# Ethernet.net
KiCad netlist of a schematic drawn in Altium Designer
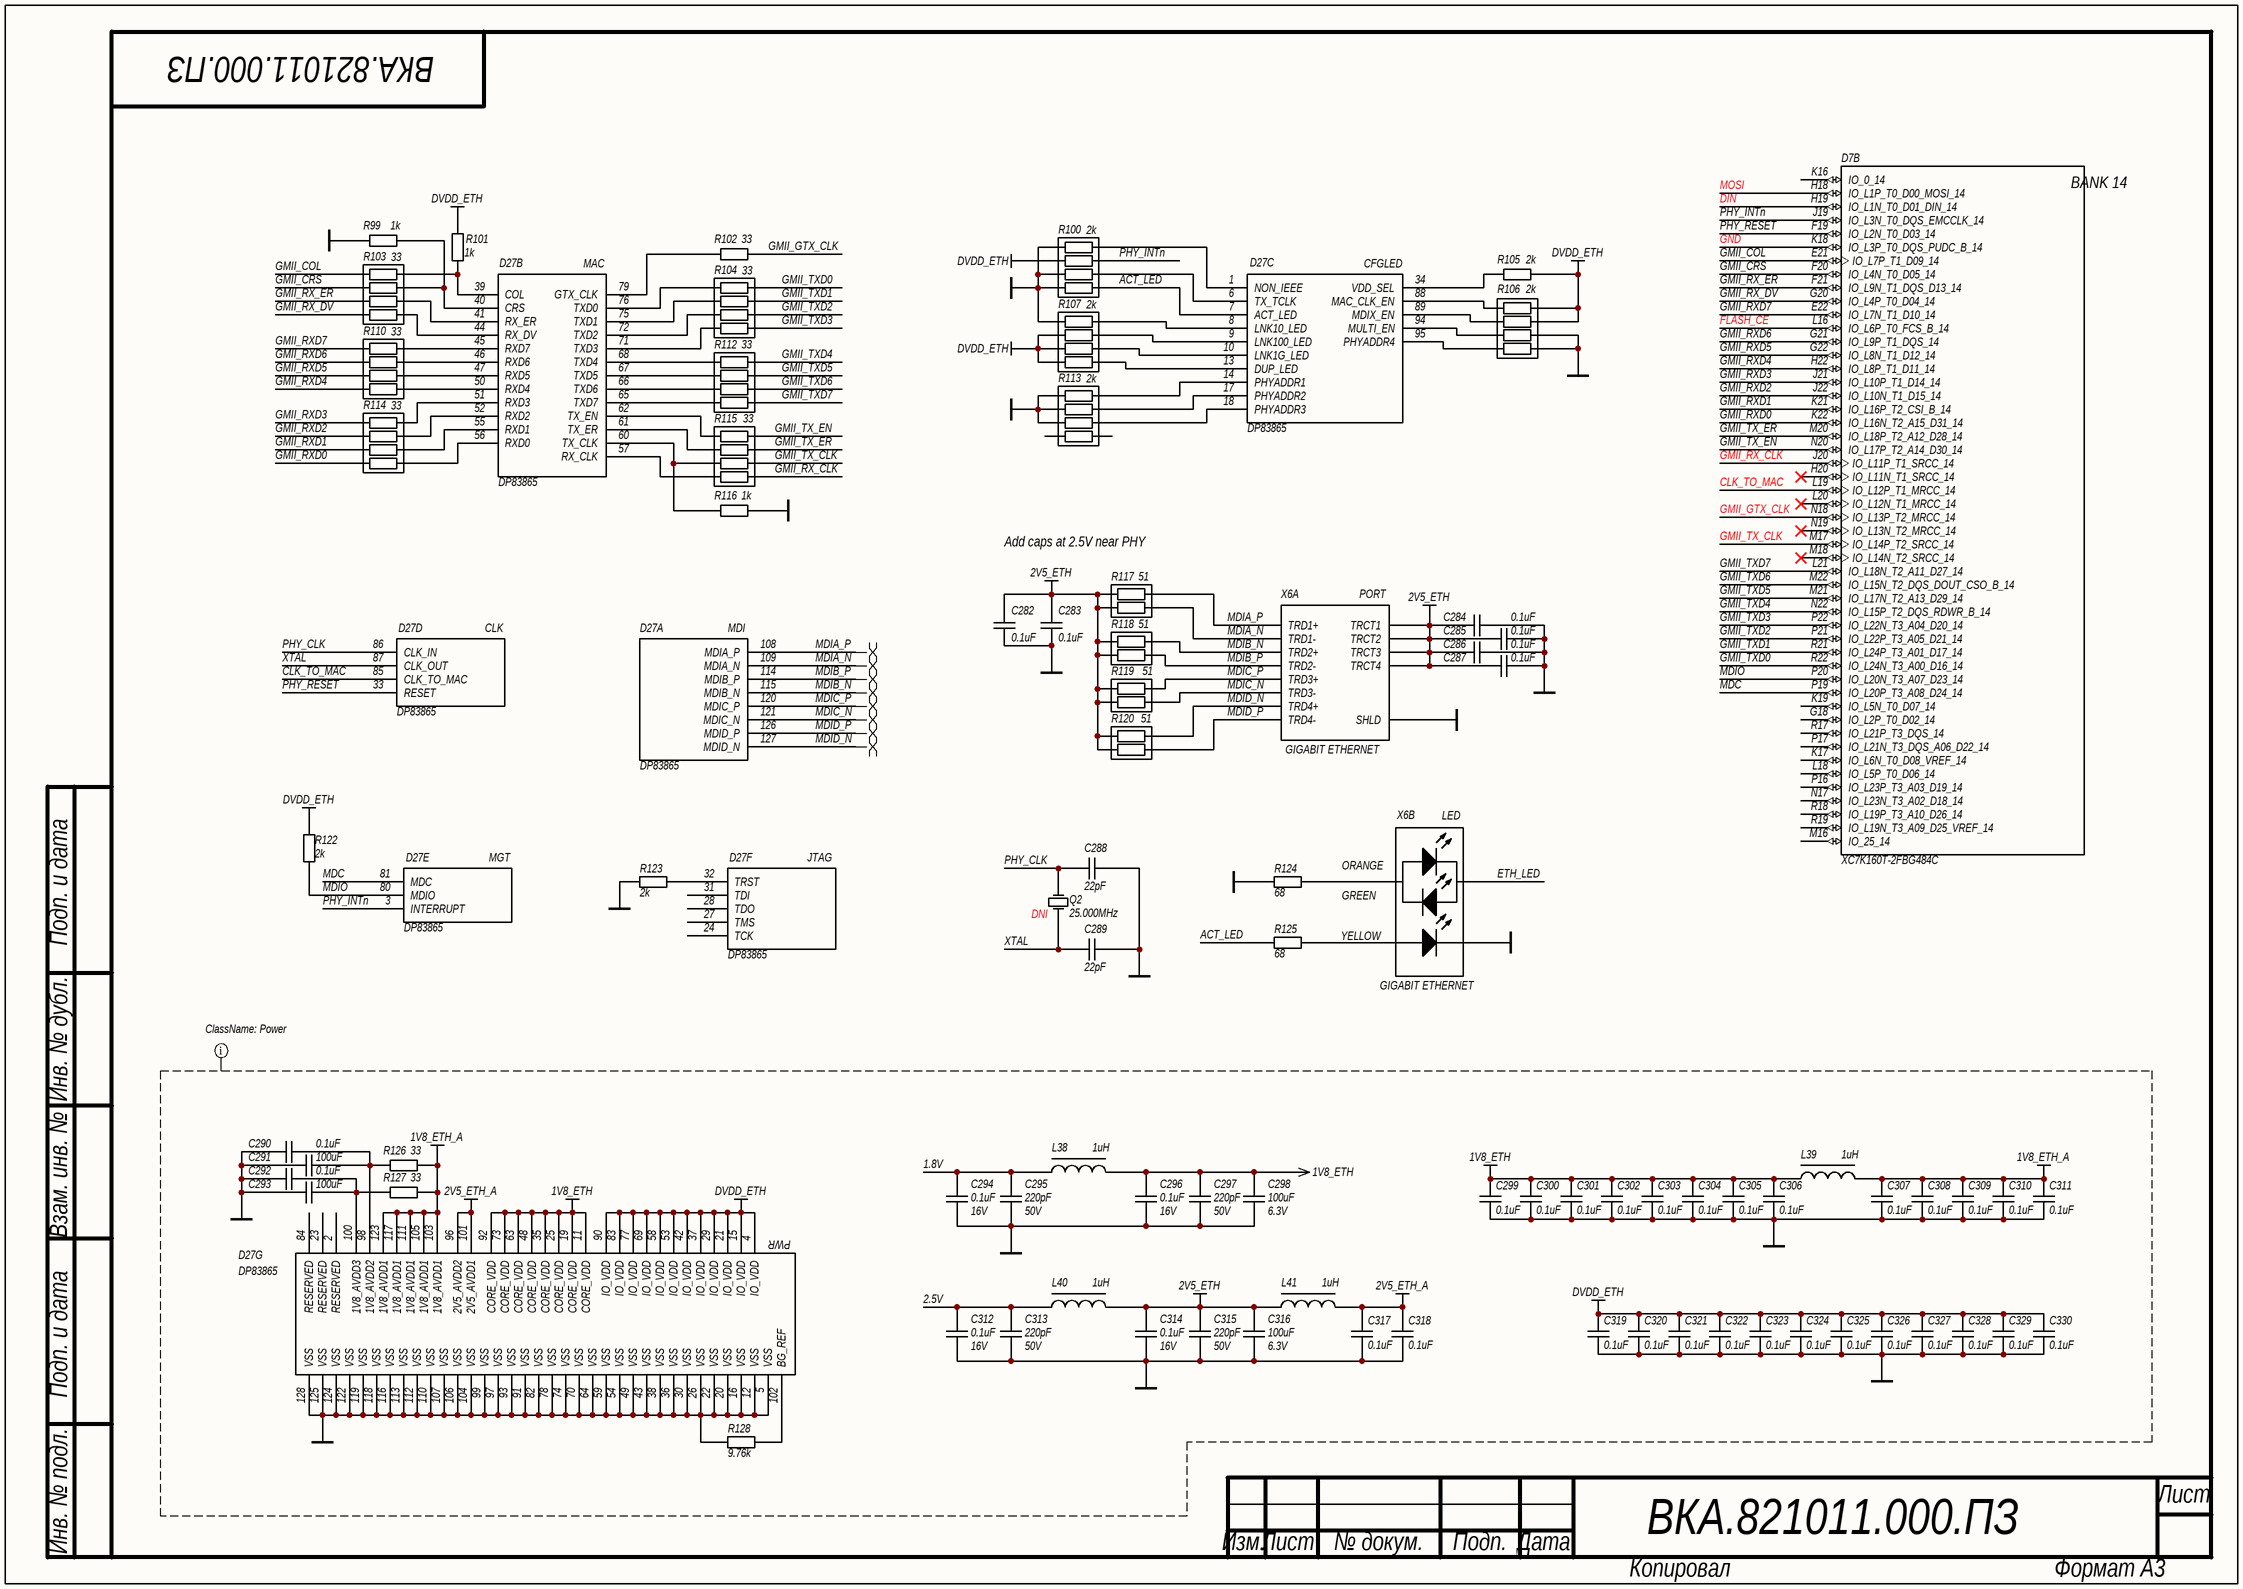
[diagram p0: Ethernet.SchDoc]

(export (version "E")
  (design (tool "Eeschema 10.0.6"))
  (components
    (comp (ref "C282")
      (value "0.1uF")
      (footprint "C0402")
      (description "SMD Capacitor")
      (fields (field (name "MANUFACTURER") "Murata") (field (name "TOLERANCE") "10%"))
      (libsource (lib "Kintex_SDR") (part "CAP"))
    )
    (comp (ref "C283")
      (value "0.1uF")
      (footprint "C0402")
      (description "SMD Capacitor")
      (fields (field (name "MANUFACTURER") "Murata") (field (name "TOLERANCE") "10%"))
      (libsource (lib "Kintex_SDR") (part "CAP"))
    )
    (comp (ref "C284")
      (value "0.1uF")
      (footprint "C0402")
      (description "SMD Capacitor")
      (fields (field (name "MANUFACTURER") "Murata") (field (name "TOLERANCE") "10%"))
      (libsource (lib "Kintex_SDR") (part "CAP"))
    )
    (comp (ref "C285")
      (value "0.1uF")
      (footprint "C0402")
      (description "SMD Capacitor")
      (fields (field (name "MANUFACTURER") "Murata") (field (name "TOLERANCE") "10%"))
      (libsource (lib "Kintex_SDR") (part "CAP"))
    )
    (comp (ref "C286")
      (value "0.1uF")
      (footprint "C0402")
      (description "SMD Capacitor")
      (fields (field (name "MANUFACTURER") "Murata") (field (name "TOLERANCE") "10%"))
      (libsource (lib "Kintex_SDR") (part "CAP"))
    )
    (comp (ref "C287")
      (value "0.1uF")
      (footprint "C0402")
      (description "SMD Capacitor")
      (fields (field (name "MANUFACTURER") "Murata") (field (name "TOLERANCE") "10%"))
      (libsource (lib "Kintex_SDR") (part "CAP"))
    )
    (comp (ref "C288")
      (value "22pF")
      (footprint "C0402")
      (description "SMD Capacitor")
      (fields (field (name "MANUFACTURER") "Murata") (field (name "TOLERANCE") "1%"))
      (libsource (lib "Kintex_SDR") (part "CAP"))
    )
    (comp (ref "C289")
      (value "22pF")
      (footprint "C0402")
      (description "SMD Capacitor")
      (fields (field (name "MANUFACTURER") "Murata") (field (name "TOLERANCE") "1%"))
      (libsource (lib "Kintex_SDR") (part "CAP"))
    )
    (comp (ref "C290")
      (value "0.1uF")
      (footprint "C0402")
      (description "SMD Capacitor")
      (fields (field (name "MANUFACTURER") "Murata") (field (name "TOLERANCE") "10%"))
      (libsource (lib "Kintex_SDR") (part "CAP"))
    )
    (comp (ref "C291")
      (value "100uF")
      (footprint "C1210")
      (description "SMD Capacitor")
      (fields (field (name "MANUFACTURER") "Murata") (field (name "TOLERANCE") "20%"))
      (libsource (lib "Kintex_SDR") (part "CAP uF"))
    )
    (comp (ref "C292")
      (value "0.1uF")
      (footprint "C0402")
      (description "SMD Capacitor")
      (fields (field (name "MANUFACTURER") "Murata") (field (name "TOLERANCE") "10%"))
      (libsource (lib "Kintex_SDR") (part "CAP"))
    )
    (comp (ref "C293")
      (value "100uF")
      (footprint "C1210")
      (description "SMD Capacitor")
      (fields (field (name "MANUFACTURER") "Murata") (field (name "TOLERANCE") "20%"))
      (libsource (lib "Kintex_SDR") (part "CAP uF"))
    )
    (comp (ref "C294")
      (value "0.1uF")
      (footprint "C0603")
      (description "SMD Capacitor")
      (fields
        (field (name "MANUFACTURER") "Murata")
        (field (name "TOLERANCE") "10%")
        (field (name "VOLTAGE") "16V")
      )
      (libsource (lib "Kintex_SDR") (part "CAP"))
    )
    (comp (ref "C295")
      (value "220pF")
      (footprint "C0603")
      (description "SMD Capacitor")
      (fields
        (field (name "MANUFACTURER") "Murata")
        (field (name "TOLERANCE") "10%")
        (field (name "VOLTAGE") "50V")
      )
      (libsource (lib "Kintex_SDR") (part "CAP"))
    )
    (comp (ref "C296")
      (value "0.1uF")
      (footprint "C0603")
      (description "SMD Capacitor")
      (fields
        (field (name "MANUFACTURER") "Murata")
        (field (name "TOLERANCE") "10%")
        (field (name "VOLTAGE") "16V")
      )
      (libsource (lib "Kintex_SDR") (part "CAP"))
    )
    (comp (ref "C297")
      (value "220pF")
      (footprint "C0603")
      (description "SMD Capacitor")
      (fields
        (field (name "MANUFACTURER") "Murata")
        (field (name "TOLERANCE") "10%")
        (field (name "VOLTAGE") "50V")
      )
      (libsource (lib "Kintex_SDR") (part "CAP"))
    )
    (comp (ref "C298")
      (value "100uF")
      (footprint "C1210")
      (description "SMD Capacitor")
      (fields
        (field (name "MANUFACTURER") "Murata")
        (field (name "TOLERANCE") "20%")
        (field (name "VOLTAGE") "6.3V")
      )
      (libsource (lib "Kintex_SDR") (part "CAP uF"))
    )
    (comp (ref "C299")
      (value "0.1uF")
      (footprint "C0402")
      (description "SMD Capacitor")
      (fields (field (name "MANUFACTURER") "Murata") (field (name "TOLERANCE") "10%"))
      (libsource (lib "Kintex_SDR") (part "CAP"))
    )
    (comp (ref "C300")
      (value "0.1uF")
      (footprint "C0402")
      (description "SMD Capacitor")
      (fields (field (name "MANUFACTURER") "Murata") (field (name "TOLERANCE") "10%"))
      (libsource (lib "Kintex_SDR") (part "CAP"))
    )
    (comp (ref "C301")
      (value "0.1uF")
      (footprint "C0402")
      (description "SMD Capacitor")
      (fields (field (name "MANUFACTURER") "Murata") (field (name "TOLERANCE") "10%"))
      (libsource (lib "Kintex_SDR") (part "CAP"))
    )
    (comp (ref "C302")
      (value "0.1uF")
      (footprint "C0402")
      (description "SMD Capacitor")
      (fields (field (name "MANUFACTURER") "Murata") (field (name "TOLERANCE") "10%"))
      (libsource (lib "Kintex_SDR") (part "CAP"))
    )
    (comp (ref "C303")
      (value "0.1uF")
      (footprint "C0402")
      (description "SMD Capacitor")
      (fields (field (name "MANUFACTURER") "Murata") (field (name "TOLERANCE") "10%"))
      (libsource (lib "Kintex_SDR") (part "CAP"))
    )
    (comp (ref "C304")
      (value "0.1uF")
      (footprint "C0402")
      (description "SMD Capacitor")
      (fields (field (name "MANUFACTURER") "Murata") (field (name "TOLERANCE") "10%"))
      (libsource (lib "Kintex_SDR") (part "CAP"))
    )
    (comp (ref "C305")
      (value "0.1uF")
      (footprint "C0402")
      (description "SMD Capacitor")
      (fields (field (name "MANUFACTURER") "Murata") (field (name "TOLERANCE") "10%"))
      (libsource (lib "Kintex_SDR") (part "CAP"))
    )
    (comp (ref "C306")
      (value "0.1uF")
      (footprint "C0402")
      (description "SMD Capacitor")
      (fields (field (name "MANUFACTURER") "Murata") (field (name "TOLERANCE") "10%"))
      (libsource (lib "Kintex_SDR") (part "CAP"))
    )
    (comp (ref "C307")
      (value "0.1uF")
      (footprint "C0402")
      (description "SMD Capacitor")
      (fields (field (name "MANUFACTURER") "Murata") (field (name "TOLERANCE") "10%"))
      (libsource (lib "Kintex_SDR") (part "CAP"))
    )
    (comp (ref "C308")
      (value "0.1uF")
      (footprint "C0402")
      (description "SMD Capacitor")
      (fields (field (name "MANUFACTURER") "Murata") (field (name "TOLERANCE") "10%"))
      (libsource (lib "Kintex_SDR") (part "CAP"))
    )
    (comp (ref "C309")
      (value "0.1uF")
      (footprint "C0402")
      (description "SMD Capacitor")
      (fields (field (name "MANUFACTURER") "Murata") (field (name "TOLERANCE") "10%"))
      (libsource (lib "Kintex_SDR") (part "CAP"))
    )
    (comp (ref "C310")
      (value "0.1uF")
      (footprint "C0402")
      (description "SMD Capacitor")
      (fields (field (name "MANUFACTURER") "Murata") (field (name "TOLERANCE") "10%"))
      (libsource (lib "Kintex_SDR") (part "CAP"))
    )
    (comp (ref "C311")
      (value "0.1uF")
      (footprint "C0402")
      (description "SMD Capacitor")
      (fields (field (name "MANUFACTURER") "Murata") (field (name "TOLERANCE") "10%"))
      (libsource (lib "Kintex_SDR") (part "CAP"))
    )
    (comp (ref "C312")
      (value "0.1uF")
      (footprint "C0603")
      (description "SMD Capacitor")
      (fields
        (field (name "MANUFACTURER") "Murata")
        (field (name "TOLERANCE") "10%")
        (field (name "VOLTAGE") "16V")
      )
      (libsource (lib "Kintex_SDR") (part "CAP"))
    )
    (comp (ref "C313")
      (value "220pF")
      (footprint "C0603")
      (description "SMD Capacitor")
      (fields
        (field (name "MANUFACTURER") "Murata")
        (field (name "TOLERANCE") "10%")
        (field (name "VOLTAGE") "50V")
      )
      (libsource (lib "Kintex_SDR") (part "CAP"))
    )
    (comp (ref "C314")
      (value "0.1uF")
      (footprint "C0603")
      (description "SMD Capacitor")
      (fields
        (field (name "MANUFACTURER") "Murata")
        (field (name "TOLERANCE") "10%")
        (field (name "VOLTAGE") "16V")
      )
      (libsource (lib "Kintex_SDR") (part "CAP"))
    )
    (comp (ref "C315")
      (value "220pF")
      (footprint "C0603")
      (description "SMD Capacitor")
      (fields
        (field (name "MANUFACTURER") "Murata")
        (field (name "TOLERANCE") "10%")
        (field (name "VOLTAGE") "50V")
      )
      (libsource (lib "Kintex_SDR") (part "CAP"))
    )
    (comp (ref "C316")
      (value "100uF")
      (footprint "C1210")
      (description "SMD Capacitor")
      (fields
        (field (name "MANUFACTURER") "Murata")
        (field (name "TOLERANCE") "20%")
        (field (name "VOLTAGE") "6.3V")
      )
      (libsource (lib "Kintex_SDR") (part "CAP uF"))
    )
    (comp (ref "C317")
      (value "0.1uF")
      (footprint "C0402")
      (description "SMD Capacitor")
      (fields (field (name "MANUFACTURER") "Murata") (field (name "TOLERANCE") "10%"))
      (libsource (lib "Kintex_SDR") (part "CAP"))
    )
    (comp (ref "C318")
      (value "0.1uF")
      (footprint "C0402")
      (description "SMD Capacitor")
      (fields (field (name "MANUFACTURER") "Murata") (field (name "TOLERANCE") "10%"))
      (libsource (lib "Kintex_SDR") (part "CAP"))
    )
    (comp (ref "C319")
      (value "0.1uF")
      (footprint "C0402")
      (description "SMD Capacitor")
      (fields (field (name "MANUFACTURER") "Murata") (field (name "TOLERANCE") "10%"))
      (libsource (lib "Kintex_SDR") (part "CAP"))
    )
    (comp (ref "C320")
      (value "0.1uF")
      (footprint "C0402")
      (description "SMD Capacitor")
      (fields (field (name "MANUFACTURER") "Murata") (field (name "TOLERANCE") "10%"))
      (libsource (lib "Kintex_SDR") (part "CAP"))
    )
    (comp (ref "C321")
      (value "0.1uF")
      (footprint "C0402")
      (description "SMD Capacitor")
      (fields (field (name "MANUFACTURER") "Murata") (field (name "TOLERANCE") "10%"))
      (libsource (lib "Kintex_SDR") (part "CAP"))
    )
    (comp (ref "C322")
      (value "0.1uF")
      (footprint "C0402")
      (description "SMD Capacitor")
      (fields (field (name "MANUFACTURER") "Murata") (field (name "TOLERANCE") "10%"))
      (libsource (lib "Kintex_SDR") (part "CAP"))
    )
    (comp (ref "C323")
      (value "0.1uF")
      (footprint "C0402")
      (description "SMD Capacitor")
      (fields (field (name "MANUFACTURER") "Murata") (field (name "TOLERANCE") "10%"))
      (libsource (lib "Kintex_SDR") (part "CAP"))
    )
    (comp (ref "C324")
      (value "0.1uF")
      (footprint "C0402")
      (description "SMD Capacitor")
      (fields (field (name "MANUFACTURER") "Murata") (field (name "TOLERANCE") "10%"))
      (libsource (lib "Kintex_SDR") (part "CAP"))
    )
    (comp (ref "C325")
      (value "0.1uF")
      (footprint "C0402")
      (description "SMD Capacitor")
      (fields (field (name "MANUFACTURER") "Murata") (field (name "TOLERANCE") "10%"))
      (libsource (lib "Kintex_SDR") (part "CAP"))
    )
    (comp (ref "C326")
      (value "0.1uF")
      (footprint "C0402")
      (description "SMD Capacitor")
      (fields (field (name "MANUFACTURER") "Murata") (field (name "TOLERANCE") "10%"))
      (libsource (lib "Kintex_SDR") (part "CAP"))
    )
    (comp (ref "C327")
      (value "0.1uF")
      (footprint "C0402")
      (description "SMD Capacitor")
      (fields (field (name "MANUFACTURER") "Murata") (field (name "TOLERANCE") "10%"))
      (libsource (lib "Kintex_SDR") (part "CAP"))
    )
    (comp (ref "C328")
      (value "0.1uF")
      (footprint "C0402")
      (description "SMD Capacitor")
      (fields (field (name "MANUFACTURER") "Murata") (field (name "TOLERANCE") "10%"))
      (libsource (lib "Kintex_SDR") (part "CAP"))
    )
    (comp (ref "C329")
      (value "0.1uF")
      (footprint "C0402")
      (description "SMD Capacitor")
      (fields (field (name "MANUFACTURER") "Murata") (field (name "TOLERANCE") "10%"))
      (libsource (lib "Kintex_SDR") (part "CAP"))
    )
    (comp (ref "C330")
      (value "0.1uF")
      (footprint "C0402")
      (description "SMD Capacitor")
      (fields (field (name "MANUFACTURER") "Murata") (field (name "TOLERANCE") "10%"))
      (libsource (lib "Kintex_SDR") (part "CAP"))
    )
    (comp (ref "D7")
      (value "XC7K160T-2FBG484C")
      (footprint "FBG484")
      (description "Xilinx 7-Series FPGA")
      (fields (field (name "MANUFACTURER") "Xilinx"))
      (libsource (lib "Kintex_SDR") (part "XC7K160T-2FBG484C"))
    )
    (comp (ref "D27")
      (value "DP83865")
      (footprint "PQFP-128")
      (description "10/100/1000 Ethernet Physical Layer")
      (libsource (lib "Kintex_SDR") (part "DP83865"))
    )
    (comp (ref "L38")
      (value "1uH")
      (footprint "L1210_Murata LQH")
      (description "Inductor Power Lines")
      (fields (field (name "MANUFACTURER") "Murata") (field (name "TOLERANCE") "5%"))
      (libsource (lib "Kintex_SDR") (part "Inductor LF"))
    )
    (comp (ref "L39")
      (value "1uH")
      (footprint "L1210_Murata LQH")
      (description "Inductor Power Lines")
      (fields (field (name "MANUFACTURER") "Murata") (field (name "TOLERANCE") "5%"))
      (libsource (lib "Kintex_SDR") (part "Inductor LF"))
    )
    (comp (ref "L40")
      (value "1uH")
      (footprint "L1210_Murata LQH")
      (description "Inductor Power Lines")
      (fields (field (name "MANUFACTURER") "Murata") (field (name "TOLERANCE") "5%"))
      (libsource (lib "Kintex_SDR") (part "Inductor LF"))
    )
    (comp (ref "L41")
      (value "1uH")
      (footprint "L1210_Murata LQH")
      (description "Inductor Power Lines")
      (fields (field (name "MANUFACTURER") "Murata") (field (name "TOLERANCE") "5%"))
      (libsource (lib "Kintex_SDR") (part "Inductor LF"))
    )
    (comp (ref "Q2")
      (value "25.000MHz")
      (footprint "SMT 5x7")
      (description "Qurtz")
      (fields
        (field (name "MANUFACTURER") "GEYER ELECTRONIC")
        (field (name "TOLERANCE") "± 30 ppm")
        (field (name "NOTE") "DNI")
      )
      (libsource (lib "Kintex_SDR") (part "Quartz"))
    )
    (comp (ref "R99")
      (value "1k")
      (footprint "R0402")
      (description "SMD Resistor")
      (fields (field (name "POWER") "0.062 Wt") (field (name "TOLERANCE") "5%"))
      (libsource (lib "Kintex_SDR") (part "RES"))
    )
    (comp (ref "R100")
      (value "2k")
      (footprint "EXN8V")
      (description "Chip Resistor Array")
      (fields (field (name "TOLERANCE") "5%") (field (name "MANUFACTURER") "Panasonic"))
      (libsource (lib "Kintex_SDR") (part "RES 4x0402"))
    )
    (comp (ref "R101")
      (value "1k")
      (footprint "R0402")
      (description "SMD Resistor")
      (fields (field (name "POWER") "0.062 Wt") (field (name "TOLERANCE") "5%"))
      (libsource (lib "") (part "RES_2"))
    )
    (comp (ref "R102")
      (value "33")
      (footprint "R0402")
      (description "SMD Resistor")
      (fields (field (name "POWER") "0.062 Wt") (field (name "TOLERANCE") "5%"))
      (libsource (lib "") (part "RES_1"))
    )
    (comp (ref "R103")
      (value "33")
      (footprint "EXN8V")
      (description "Chip Resistor Array")
      (fields (field (name "TOLERANCE") "5%") (field (name "MANUFACTURER") "Panasonic"))
      (libsource (lib "Kintex_SDR") (part "RES 4x0402"))
    )
    (comp (ref "R104")
      (value "33")
      (footprint "EXN8V")
      (description "Chip Resistor Array")
      (fields (field (name "TOLERANCE") "5%") (field (name "MANUFACTURER") "Panasonic"))
      (libsource (lib "Kintex_SDR") (part "RES 4x0402"))
    )
    (comp (ref "R105")
      (value "2k")
      (footprint "R0402")
      (description "SMD Resistor")
      (fields (field (name "POWER") "0.062 Wt") (field (name "TOLERANCE") "5%"))
      (libsource (lib "") (part "RES_1"))
    )
    (comp (ref "R106")
      (value "2k")
      (footprint "EXN8V")
      (description "Chip Resistor Array")
      (fields (field (name "TOLERANCE") "5%") (field (name "MANUFACTURER") "Panasonic"))
      (libsource (lib "") (part "RES 4x0402_2"))
    )
    (comp (ref "R107")
      (value "2k")
      (footprint "EXN8V")
      (description "Chip Resistor Array")
      (fields (field (name "TOLERANCE") "5%") (field (name "MANUFACTURER") "Panasonic"))
      (libsource (lib "Kintex_SDR") (part "RES 4x0402"))
    )
    (comp (ref "R110")
      (value "33")
      (footprint "EXN8V")
      (description "Chip Resistor Array")
      (fields (field (name "TOLERANCE") "5%") (field (name "MANUFACTURER") "Panasonic"))
      (libsource (lib "Kintex_SDR") (part "RES 4x0402"))
    )
    (comp (ref "R112")
      (value "33")
      (footprint "EXN8V")
      (description "Chip Resistor Array")
      (fields (field (name "TOLERANCE") "5%") (field (name "MANUFACTURER") "Panasonic"))
      (libsource (lib "") (part "RES 4x0402_1"))
    )
    (comp (ref "R113")
      (value "2k")
      (footprint "EXN8V")
      (description "Chip Resistor Array")
      (fields (field (name "TOLERANCE") "5%") (field (name "MANUFACTURER") "Panasonic"))
      (libsource (lib "Kintex_SDR") (part "RES 4x0402"))
    )
    (comp (ref "R114")
      (value "33")
      (footprint "EXN8V")
      (description "Chip Resistor Array")
      (fields (field (name "TOLERANCE") "5%") (field (name "MANUFACTURER") "Panasonic"))
      (libsource (lib "Kintex_SDR") (part "RES 4x0402"))
    )
    (comp (ref "R115")
      (value "33")
      (footprint "EXN8V")
      (description "Chip Resistor Array")
      (fields (field (name "TOLERANCE") "5%") (field (name "MANUFACTURER") "Panasonic"))
      (libsource (lib "") (part "RES 4x0402_1"))
    )
    (comp (ref "R116")
      (value "1k")
      (footprint "R0402")
      (description "SMD Resistor")
      (fields (field (name "POWER") "0.062 Wt") (field (name "TOLERANCE") "5%"))
      (libsource (lib "") (part "RES_1"))
    )
    (comp (ref "R117")
      (value "51")
      (footprint "EX24V")
      (description "Chip Resistor Array")
      (fields (field (name "TOLERANCE") "5%") (field (name "MANUFACTURER") "Panasonic"))
      (libsource (lib "") (part "RES 2x0402_1"))
    )
    (comp (ref "R118")
      (value "51")
      (footprint "EX24V")
      (description "Chip Resistor Array")
      (fields (field (name "TOLERANCE") "5%") (field (name "MANUFACTURER") "Panasonic"))
      (libsource (lib "") (part "RES 2x0402_1"))
    )
    (comp (ref "R119")
      (value "51")
      (footprint "EX24V")
      (description "Chip Resistor Array")
      (fields (field (name "TOLERANCE") "5%") (field (name "MANUFACTURER") "Panasonic"))
      (libsource (lib "Kintex_SDR") (part "RES 2x0402"))
    )
    (comp (ref "R120")
      (value "51")
      (footprint "EX24V")
      (description "Chip Resistor Array")
      (fields (field (name "TOLERANCE") "5%") (field (name "MANUFACTURER") "Panasonic"))
      (libsource (lib "Kintex_SDR") (part "RES 2x0402"))
    )
    (comp (ref "R122")
      (value "2k")
      (footprint "R0402")
      (description "SMD Resistor")
      (fields (field (name "POWER") "0.062 Wt") (field (name "TOLERANCE") "5%"))
      (libsource (lib "") (part "RES_3"))
    )
    (comp (ref "R123")
      (value "2k")
      (footprint "R0402")
      (description "SMD Resistor")
      (fields (field (name "POWER") "0.062 Wt") (field (name "TOLERANCE") "5%"))
      (libsource (lib "") (part "RES_1"))
    )
    (comp (ref "R124")
      (value "68")
      (footprint "R0402")
      (description "SMD Resistor")
      (fields (field (name "POWER") "0.062 Wt") (field (name "TOLERANCE") "5%"))
      (libsource (lib "") (part "RES_1"))
    )
    (comp (ref "R125")
      (value "68")
      (footprint "R0402")
      (description "SMD Resistor")
      (fields (field (name "POWER") "0.062 Wt") (field (name "TOLERANCE") "5%"))
      (libsource (lib "") (part "RES_1"))
    )
    (comp (ref "R126")
      (value "33")
      (footprint "R0402")
      (description "SMD Resistor")
      (fields (field (name "POWER") "0.062 Wt") (field (name "TOLERANCE") "5%"))
      (libsource (lib "Kintex_SDR") (part "RES"))
    )
    (comp (ref "R127")
      (value "33")
      (footprint "R0402")
      (description "SMD Resistor")
      (fields (field (name "POWER") "0.062 Wt") (field (name "TOLERANCE") "5%"))
      (libsource (lib "Kintex_SDR") (part "RES"))
    )
    (comp (ref "R128")
      (value "9.76k")
      (footprint "R0402")
      (description "SMD Resistor")
      (fields (field (name "POWER") "0.062 Wt") (field (name "TOLERANCE") "5%"))
      (libsource (lib "Kintex_SDR") (part "RES"))
    )
    (comp (ref "X6")
      (value "GIGABIT ETHERNET")
      (footprint "0826-1X1T-23-F")
      (description "Gigabit Ethernet Single Port with LEDs")
      (libsource (lib "Kintex_SDR") (part "0826-1X1T-23-F"))
    )
  )
  (nets
    (net (code "1") (name "/1.8V") (class "Default")
      (node (ref "C294") (pin "2") (pinfunction "2_2") (pintype "passive"))
      (node (ref "C295") (pin "2") (pinfunction "2_2") (pintype "passive"))
      (node (ref "L38") (pin "1") (pinfunction "1_1") (pintype "passive"))
    )
    (net (code "2") (name "/2.5V") (class "Default")
      (node (ref "C312") (pin "2") (pinfunction "2_2") (pintype "passive"))
      (node (ref "C313") (pin "2") (pinfunction "2_2") (pintype "passive"))
      (node (ref "L40") (pin "1") (pinfunction "1_1") (pintype "passive"))
    )
    (net (code "3") (name "/ACT_LED") (class "Default")
      (node (ref "D27") (pin "7") (pinfunction "ACT_LED_7") (pintype "passive"))
      (node (ref "R100") (pin "5") (pinfunction "5_5") (pintype "passive"))
      (node (ref "R125") (pin "1") (pinfunction "1_1") (pintype "passive"))
    )
    (net (code "4") (name "/CLK_TO_MAC") (class "Default")
      (node (ref "D27") (pin "85") (pinfunction "CLK_TO_MAC_85") (pintype "passive"))
      (node (ref "D7") (pin "L19") (pinfunction "IO_L12P_T1_MRCC_14_L19") (pintype "bidirectional"))
    )
    (net (code "5") (name "/DIN") (class "Default")
      (node (ref "D7") (pin "H19") (pinfunction "IO_L1N_T0_D01_DIN_14_H19") (pintype "bidirectional"))
    )
    (net (code "6") (name "/ETH_LED") (class "Default")
      (node (ref "X6") (pin "16") (pinfunction "LED2_16") (pintype "passive"))
    )
    (net (code "7") (name "/FLASH_CE") (class "Default")
      (node (ref "D7") (pin "L16") (pinfunction "IO_L6P_T0_FCS_B_14_L16") (pintype "bidirectional"))
    )
    (net (code "8") (name "/GMII_COL") (class "Default")
      (node (ref "D7") (pin "E21") (pinfunction "IO_L7P_T1_D09_14_E21") (pintype "bidirectional"))
      (node (ref "R103") (pin "1") (pinfunction "1_1") (pintype "passive"))
    )
    (net (code "9") (name "/GMII_CRS") (class "Default")
      (node (ref "D7") (pin "F20") (pinfunction "IO_L4N_T0_D05_14_F20") (pintype "bidirectional"))
      (node (ref "R103") (pin "2") (pinfunction "2_2") (pintype "passive"))
    )
    (net (code "10") (name "/GMII_GTX_CLK") (class "Default")
      (node (ref "D7") (pin "N18") (pinfunction "IO_L13P_T2_MRCC_14_N18") (pintype "bidirectional"))
      (node (ref "R102") (pin "2") (pinfunction "2_2") (pintype "passive"))
    )
    (net (code "11") (name "/GMII_RXD0") (class "Default")
      (node (ref "D7") (pin "K22") (pinfunction "IO_L16N_T2_A15_D31_14_K22") (pintype "bidirectional"))
      (node (ref "R114") (pin "4") (pinfunction "4_4") (pintype "passive"))
    )
    (net (code "12") (name "/GMII_RXD1") (class "Default")
      (node (ref "D7") (pin "K21") (pinfunction "IO_L16P_T2_CSI_B_14_K21") (pintype "bidirectional"))
      (node (ref "R114") (pin "3") (pinfunction "3_3") (pintype "passive"))
    )
    (net (code "13") (name "/GMII_RXD2") (class "Default")
      (node (ref "D7") (pin "J22") (pinfunction "IO_L10N_T1_D15_14_J22") (pintype "bidirectional"))
      (node (ref "R114") (pin "2") (pinfunction "2_2") (pintype "passive"))
    )
    (net (code "14") (name "/GMII_RXD3") (class "Default")
      (node (ref "D7") (pin "J21") (pinfunction "IO_L10P_T1_D14_14_J21") (pintype "bidirectional"))
      (node (ref "R114") (pin "1") (pinfunction "1_1") (pintype "passive"))
    )
    (net (code "15") (name "/GMII_RXD4") (class "Default")
      (node (ref "D7") (pin "H22") (pinfunction "IO_L8P_T1_D11_14_H22") (pintype "bidirectional"))
      (node (ref "R110") (pin "4") (pinfunction "4_4") (pintype "passive"))
    )
    (net (code "16") (name "/GMII_RXD5") (class "Default")
      (node (ref "D7") (pin "G22") (pinfunction "IO_L8N_T1_D12_14_G22") (pintype "bidirectional"))
      (node (ref "R110") (pin "3") (pinfunction "3_3") (pintype "passive"))
    )
    (net (code "17") (name "/GMII_RXD6") (class "Default")
      (node (ref "D7") (pin "G21") (pinfunction "IO_L9P_T1_DQS_14_G21") (pintype "bidirectional"))
      (node (ref "R110") (pin "2") (pinfunction "2_2") (pintype "passive"))
    )
    (net (code "18") (name "/GMII_RXD7") (class "Default")
      (node (ref "D7") (pin "E22") (pinfunction "IO_L7N_T1_D10_14_E22") (pintype "bidirectional"))
      (node (ref "R110") (pin "1") (pinfunction "1_1") (pintype "passive"))
    )
    (net (code "19") (name "/GMII_RX_CLK") (class "Default")
      (node (ref "D7") (pin "J20") (pinfunction "IO_L11P_T1_SRCC_14_J20") (pintype "bidirectional"))
      (node (ref "R115") (pin "1") (pinfunction "1_1") (pintype "passive"))
    )
    (net (code "20") (name "/GMII_RX_DV") (class "Default")
      (node (ref "D7") (pin "G20") (pinfunction "IO_L4P_T0_D04_14_G20") (pintype "bidirectional"))
      (node (ref "R103") (pin "4") (pinfunction "4_4") (pintype "passive"))
    )
    (net (code "21") (name "/GMII_RX_ER") (class "Default")
      (node (ref "D7") (pin "F21") (pinfunction "IO_L9N_T1_DQS_D13_14_F21") (pintype "bidirectional"))
      (node (ref "R103") (pin "3") (pinfunction "3_3") (pintype "passive"))
    )
    (net (code "22") (name "/GMII_TXD0") (class "Default")
      (node (ref "D7") (pin "R22") (pinfunction "IO_L24N_T3_A00_D16_14_R22") (pintype "bidirectional"))
      (node (ref "R104") (pin "8") (pinfunction "8_8") (pintype "passive"))
    )
    (net (code "23") (name "/GMII_TXD1") (class "Default")
      (node (ref "D7") (pin "R21") (pinfunction "IO_L24P_T3_A01_D17_14_R21") (pintype "bidirectional"))
      (node (ref "R104") (pin "7") (pinfunction "7_7") (pintype "passive"))
    )
    (net (code "24") (name "/GMII_TXD2") (class "Default")
      (node (ref "D7") (pin "P21") (pinfunction "IO_L22P_T3_A05_D21_14_P21") (pintype "bidirectional"))
      (node (ref "R104") (pin "6") (pinfunction "6_6") (pintype "passive"))
    )
    (net (code "25") (name "/GMII_TXD3") (class "Default")
      (node (ref "D7") (pin "P22") (pinfunction "IO_L22N_T3_A04_D20_14_P22") (pintype "bidirectional"))
      (node (ref "R104") (pin "5") (pinfunction "5_5") (pintype "passive"))
    )
    (net (code "26") (name "/GMII_TXD4") (class "Default")
      (node (ref "D7") (pin "N22") (pinfunction "IO_L15P_T2_DQS_RDWR_B_14_N22") (pintype "bidirectional"))
      (node (ref "R112") (pin "4") (pinfunction "4_4") (pintype "passive"))
    )
    (net (code "27") (name "/GMII_TXD5") (class "Default")
      (node (ref "D7") (pin "M21") (pinfunction "IO_L17N_T2_A13_D29_14_M21") (pintype "bidirectional"))
      (node (ref "R112") (pin "3") (pinfunction "3_3") (pintype "passive"))
    )
    (net (code "28") (name "/GMII_TXD6") (class "Default")
      (node (ref "D7") (pin "M22") (pinfunction "IO_L15N_T2_DQS_DOUT_CSO_B_14_M22") (pintype "bidirectional"))
      (node (ref "R112") (pin "2") (pinfunction "2_2") (pintype "passive"))
    )
    (net (code "29") (name "/GMII_TXD7") (class "Default")
      (node (ref "D7") (pin "L21") (pinfunction "IO_L18N_T2_A11_D27_14_L21") (pintype "bidirectional"))
      (node (ref "R112") (pin "1") (pinfunction "1_1") (pintype "passive"))
    )
    (net (code "30") (name "/GMII_TX_CLK") (class "Default")
      (node (ref "D7") (pin "M17") (pinfunction "IO_L14P_T2_SRCC_14_M17") (pintype "bidirectional"))
      (node (ref "R115") (pin "2") (pinfunction "2_2") (pintype "passive"))
    )
    (net (code "31") (name "/GMII_TX_EN") (class "Default")
      (node (ref "D7") (pin "N20") (pinfunction "IO_L17P_T2_A14_D30_14_N20") (pintype "bidirectional"))
      (node (ref "R115") (pin "4") (pinfunction "4_4") (pintype "passive"))
    )
    (net (code "32") (name "/GMII_TX_ER") (class "Default")
      (node (ref "D7") (pin "M20") (pinfunction "IO_L18P_T2_A12_D28_14_M20") (pintype "bidirectional"))
      (node (ref "R115") (pin "3") (pinfunction "3_3") (pintype "passive"))
    )
    (net (code "33") (name "/MDC") (class "Default")
      (node (ref "D27") (pin "81") (pinfunction "MDC_81") (pintype "passive"))
      (node (ref "D7") (pin "P19") (pinfunction "IO_L20P_T3_A08_D24_14_P19") (pintype "bidirectional"))
    )
    (net (code "34") (name "/MDIA_N") (class "Default")
      (node (ref "D27") (pin "109") (pinfunction "MDIA_N_109") (pintype "passive"))
      (node (ref "R117") (pin "3") (pinfunction "3_3") (pintype "passive"))
      (node (ref "X6") (pin "10") (pinfunction "TRD1-_10") (pintype "passive"))
    )
    (net (code "35") (name "/MDIA_P") (class "Default")
      (node (ref "D27") (pin "108") (pinfunction "MDIA_P_108") (pintype "passive"))
      (node (ref "R117") (pin "4") (pinfunction "4_4") (pintype "passive"))
      (node (ref "X6") (pin "11") (pinfunction "TRD1+_11") (pintype "passive"))
    )
    (net (code "36") (name "/MDIB_N") (class "Default")
      (node (ref "D27") (pin "115") (pinfunction "MDIB_N_115") (pintype "passive"))
      (node (ref "R118") (pin "4") (pinfunction "4_4") (pintype "passive"))
      (node (ref "X6") (pin "4") (pinfunction "TRD2+_4") (pintype "passive"))
    )
    (net (code "37") (name "/MDIB_P") (class "Default")
      (node (ref "D27") (pin "114") (pinfunction "MDIB_P_114") (pintype "passive"))
      (node (ref "R118") (pin "3") (pinfunction "3_3") (pintype "passive"))
      (node (ref "X6") (pin "5") (pinfunction "TRD2-_5") (pintype "passive"))
    )
    (net (code "38") (name "/MDIC_N") (class "Default")
      (node (ref "D27") (pin "121") (pinfunction "MDIC_N_121") (pintype "passive"))
      (node (ref "R119") (pin "4") (pinfunction "4_4") (pintype "passive"))
      (node (ref "X6") (pin "2") (pinfunction "TRD3-_2") (pintype "passive"))
    )
    (net (code "39") (name "/MDIC_P") (class "Default")
      (node (ref "D27") (pin "120") (pinfunction "MDIC_P_120") (pintype "passive"))
      (node (ref "R119") (pin "3") (pinfunction "3_3") (pintype "passive"))
      (node (ref "X6") (pin "3") (pinfunction "TRD3+_3") (pintype "passive"))
    )
    (net (code "40") (name "/MDID_N") (class "Default")
      (node (ref "D27") (pin "127") (pinfunction "MDID_N_127") (pintype "passive"))
      (node (ref "R120") (pin "3") (pinfunction "3_3") (pintype "passive"))
      (node (ref "X6") (pin "8") (pinfunction "TRD4+_8") (pintype "passive"))
    )
    (net (code "41") (name "/MDID_P") (class "Default")
      (node (ref "D27") (pin "126") (pinfunction "MDID_P_126") (pintype "passive"))
      (node (ref "R120") (pin "4") (pinfunction "4_4") (pintype "passive"))
      (node (ref "X6") (pin "9") (pinfunction "TRD4-_9") (pintype "passive"))
    )
    (net (code "42") (name "/MDIO") (class "Default")
      (node (ref "D27") (pin "80") (pinfunction "MDIO_80") (pintype "passive"))
      (node (ref "D7") (pin "P20") (pinfunction "IO_L20N_T3_A07_D23_14_P20") (pintype "bidirectional"))
      (node (ref "R122") (pin "2") (pinfunction "2_2") (pintype "passive"))
    )
    (net (code "43") (name "/MOSI") (class "Default")
      (node (ref "D7") (pin "H18") (pinfunction "IO_L1P_T0_D00_MOSI_14_H18") (pintype "bidirectional"))
    )
    (net (code "44") (name "/PHY_CLK") (class "Default")
      (node (ref "C288") (pin "1") (pinfunction "1_1") (pintype "passive"))
      (node (ref "D27") (pin "86") (pinfunction "CLK_IN_86") (pintype "passive"))
      (node (ref "Q2") (pin "3") (pinfunction "OSC2_3") (pintype "passive"))
    )
    (net (code "45") (name "/PHY_INTn") (class "Default")
      (node (ref "D27") (pin "3") (pinfunction "INTERRUPT_3") (pintype "passive"))
      (node (ref "D7") (pin "J19") (pinfunction "IO_L3N_T0_DQS_EMCCLK_14_J19") (pintype "bidirectional"))
      (node (ref "R100") (pin "7") (pinfunction "7_7") (pintype "passive"))
    )
    (net (code "46") (name "/PHY_RESET") (class "Default")
      (node (ref "D27") (pin "33") (pinfunction "RESET_33") (pintype "passive"))
      (node (ref "D7") (pin "F19") (pinfunction "IO_L2N_T0_D03_14_F19") (pintype "bidirectional"))
    )
    (net (code "47") (name "/XTAL") (class "Default")
      (node (ref "C289") (pin "1") (pinfunction "1_1") (pintype "passive"))
      (node (ref "D27") (pin "87") (pinfunction "CLK_OUT_87") (pintype "passive"))
      (node (ref "Q2") (pin "1") (pinfunction "OSC1_1") (pintype "passive"))
    )
    (net (code "48") (name "1V8_ETH") (class "Default")
      (node (ref "C296") (pin "2") (pinfunction "2_2") (pintype "passive"))
      (node (ref "C297") (pin "2") (pinfunction "2_2") (pintype "passive"))
      (node (ref "C298") (pin "2") (pinfunction "2_2") (pintype "passive"))
      (node (ref "C299") (pin "2") (pinfunction "2_2") (pintype "passive"))
      (node (ref "C300") (pin "2") (pinfunction "2_2") (pintype "passive"))
      (node (ref "C301") (pin "2") (pinfunction "2_2") (pintype "passive"))
      (node (ref "C302") (pin "2") (pinfunction "2_2") (pintype "passive"))
      (node (ref "C303") (pin "2") (pinfunction "2_2") (pintype "passive"))
      (node (ref "C304") (pin "2") (pinfunction "2_2") (pintype "passive"))
      (node (ref "C305") (pin "2") (pinfunction "2_2") (pintype "passive"))
      (node (ref "C306") (pin "2") (pinfunction "2_2") (pintype "passive"))
      (node (ref "D27") (pin "11") (pinfunction "CORE_VDD_11") (pintype "passive"))
      (node (ref "D27") (pin "19") (pinfunction "CORE_VDD_19") (pintype "passive"))
      (node (ref "D27") (pin "25") (pinfunction "CORE_VDD_25") (pintype "passive"))
      (node (ref "D27") (pin "35") (pinfunction "CORE_VDD_35") (pintype "passive"))
      (node (ref "D27") (pin "48") (pinfunction "CORE_VDD_48") (pintype "passive"))
      (node (ref "D27") (pin "63") (pinfunction "CORE_VDD_63") (pintype "passive"))
      (node (ref "D27") (pin "73") (pinfunction "CORE_VDD_73") (pintype "passive"))
      (node (ref "D27") (pin "92") (pinfunction "CORE_VDD_92") (pintype "passive"))
      (node (ref "L38") (pin "2") (pinfunction "2_2") (pintype "passive"))
      (node (ref "L39") (pin "1") (pinfunction "1_1") (pintype "passive"))
    )
    (net (code "49") (name "1V8_ETH_A") (class "Default")
      (node (ref "C307") (pin "2") (pinfunction "2_2") (pintype "passive"))
      (node (ref "C308") (pin "2") (pinfunction "2_2") (pintype "passive"))
      (node (ref "C309") (pin "2") (pinfunction "2_2") (pintype "passive"))
      (node (ref "C310") (pin "2") (pinfunction "2_2") (pintype "passive"))
      (node (ref "C311") (pin "2") (pinfunction "2_2") (pintype "passive"))
      (node (ref "D27") (pin "103") (pinfunction "1V8_AVDD1_103") (pintype "passive"))
      (node (ref "D27") (pin "105") (pinfunction "1V8_AVDD1_105") (pintype "passive"))
      (node (ref "D27") (pin "111") (pinfunction "1V8_AVDD1_111") (pintype "passive"))
      (node (ref "D27") (pin "117") (pinfunction "1V8_AVDD1_117") (pintype "passive"))
      (node (ref "D27") (pin "123") (pinfunction "1V8_AVDD1_123") (pintype "passive"))
      (node (ref "L39") (pin "2") (pinfunction "2_2") (pintype "passive"))
      (node (ref "R126") (pin "1") (pinfunction "1_1") (pintype "passive"))
      (node (ref "R127") (pin "1") (pinfunction "1_1") (pintype "passive"))
    )
    (net (code "50") (name "2V5_ETH") (class "Default")
      (node (ref "C282") (pin "1") (pinfunction "1_1") (pintype "passive"))
      (node (ref "C283") (pin "1") (pinfunction "1_1") (pintype "passive"))
      (node (ref "C284") (pin "2") (pinfunction "2_2") (pintype "passive"))
      (node (ref "C285") (pin "2") (pinfunction "2_2") (pintype "passive"))
      (node (ref "C286") (pin "2") (pinfunction "2_2") (pintype "passive"))
      (node (ref "C287") (pin "2") (pinfunction "2_2") (pintype "passive"))
      (node (ref "C314") (pin "2") (pinfunction "2_2") (pintype "passive"))
      (node (ref "C315") (pin "2") (pinfunction "2_2") (pintype "passive"))
      (node (ref "C316") (pin "2") (pinfunction "2_2") (pintype "passive"))
      (node (ref "L40") (pin "2") (pinfunction "2_2") (pintype "passive"))
      (node (ref "L41") (pin "1") (pinfunction "1_1") (pintype "passive"))
      (node (ref "R117") (pin "1") (pinfunction "1_1") (pintype "passive"))
      (node (ref "R117") (pin "2") (pinfunction "2_2") (pintype "passive"))
      (node (ref "R118") (pin "1") (pinfunction "1_1") (pintype "passive"))
      (node (ref "R118") (pin "2") (pinfunction "2_2") (pintype "passive"))
      (node (ref "R119") (pin "1") (pinfunction "1_1") (pintype "passive"))
      (node (ref "R119") (pin "2") (pinfunction "2_2") (pintype "passive"))
      (node (ref "R120") (pin "1") (pinfunction "1_1") (pintype "passive"))
      (node (ref "R120") (pin "2") (pinfunction "2_2") (pintype "passive"))
      (node (ref "X6") (pin "1") (pinfunction "TRCT3_1") (pintype "passive"))
      (node (ref "X6") (pin "12") (pinfunction "TRCT1_12") (pintype "passive"))
      (node (ref "X6") (pin "6") (pinfunction "TRCT2_6") (pintype "passive"))
      (node (ref "X6") (pin "7") (pinfunction "TRCT4_7") (pintype "passive"))
    )
    (net (code "51") (name "2V5_ETH_A") (class "Default")
      (node (ref "C317") (pin "2") (pinfunction "2_2") (pintype "passive"))
      (node (ref "C318") (pin "2") (pinfunction "2_2") (pintype "passive"))
      (node (ref "D27") (pin "101") (pinfunction "2V5_AVDD1_101") (pintype "passive"))
      (node (ref "D27") (pin "96") (pinfunction "2V5_AVDD2_96") (pintype "passive"))
      (node (ref "L41") (pin "2") (pinfunction "2_2") (pintype "passive"))
    )
    (net (code "52") (name "DVDD_ETH") (class "Default")
      (node (ref "C319") (pin "2") (pinfunction "2_2") (pintype "passive"))
      (node (ref "C320") (pin "2") (pinfunction "2_2") (pintype "passive"))
      (node (ref "C321") (pin "2") (pinfunction "2_2") (pintype "passive"))
      (node (ref "C322") (pin "2") (pinfunction "2_2") (pintype "passive"))
      (node (ref "C323") (pin "2") (pinfunction "2_2") (pintype "passive"))
      (node (ref "C324") (pin "2") (pinfunction "2_2") (pintype "passive"))
      (node (ref "C325") (pin "2") (pinfunction "2_2") (pintype "passive"))
      (node (ref "C326") (pin "2") (pinfunction "2_2") (pintype "passive"))
      (node (ref "C327") (pin "2") (pinfunction "2_2") (pintype "passive"))
      (node (ref "C328") (pin "2") (pinfunction "2_2") (pintype "passive"))
      (node (ref "C329") (pin "2") (pinfunction "2_2") (pintype "passive"))
      (node (ref "C330") (pin "2") (pinfunction "2_2") (pintype "passive"))
      (node (ref "D27") (pin "15") (pinfunction "IO_VDD_15") (pintype "passive"))
      (node (ref "D27") (pin "21") (pinfunction "IO_VDD_21") (pintype "passive"))
      (node (ref "D27") (pin "29") (pinfunction "IO_VDD_29") (pintype "passive"))
      (node (ref "D27") (pin "37") (pinfunction "IO_VDD_37") (pintype "passive"))
      (node (ref "D27") (pin "4") (pinfunction "IO_VDD_4") (pintype "passive"))
      (node (ref "D27") (pin "42") (pinfunction "IO_VDD_42") (pintype "passive"))
      (node (ref "D27") (pin "53") (pinfunction "IO_VDD_53") (pintype "passive"))
      (node (ref "D27") (pin "58") (pinfunction "IO_VDD_58") (pintype "passive"))
      (node (ref "D27") (pin "69") (pinfunction "IO_VDD_69") (pintype "passive"))
      (node (ref "D27") (pin "77") (pinfunction "IO_VDD_77") (pintype "passive"))
      (node (ref "D27") (pin "83") (pinfunction "IO_VDD_83") (pintype "passive"))
      (node (ref "D27") (pin "90") (pinfunction "IO_VDD_90") (pintype "passive"))
      (node (ref "R100") (pin "2") (pinfunction "2_2") (pintype "passive"))
      (node (ref "R101") (pin "2") (pinfunction "2_2") (pintype "passive"))
      (node (ref "R105") (pin "2") (pinfunction "2_2") (pintype "passive"))
      (node (ref "R106") (pin "5") (pinfunction "5_5") (pintype "passive"))
      (node (ref "R106") (pin "6") (pinfunction "6_6") (pintype "passive"))
      (node (ref "R107") (pin "2") (pinfunction "2_2") (pintype "passive"))
      (node (ref "R107") (pin "3") (pinfunction "3_3") (pintype "passive"))
      (node (ref "R107") (pin "4") (pinfunction "4_4") (pintype "passive"))
      (node (ref "R122") (pin "1") (pinfunction "1_1") (pintype "passive"))
    )
    (net (code "53") (name "GND") (class "Default")
      (node (ref "C282") (pin "2") (pinfunction "2_2") (pintype "passive"))
      (node (ref "C283") (pin "2") (pinfunction "2_2") (pintype "passive"))
      (node (ref "C284") (pin "1") (pinfunction "1_1") (pintype "passive"))
      (node (ref "C285") (pin "1") (pinfunction "1_1") (pintype "passive"))
      (node (ref "C286") (pin "1") (pinfunction "1_1") (pintype "passive"))
      (node (ref "C287") (pin "1") (pinfunction "1_1") (pintype "passive"))
      (node (ref "C288") (pin "2") (pinfunction "2_2") (pintype "passive"))
      (node (ref "C289") (pin "2") (pinfunction "2_2") (pintype "passive"))
      (node (ref "C290") (pin "2") (pinfunction "2_2") (pintype "passive"))
      (node (ref "C291") (pin "2") (pinfunction "2_2") (pintype "passive"))
      (node (ref "C292") (pin "2") (pinfunction "2_2") (pintype "passive"))
      (node (ref "C293") (pin "2") (pinfunction "2_2") (pintype "passive"))
      (node (ref "C294") (pin "1") (pinfunction "1_1") (pintype "passive"))
      (node (ref "C295") (pin "1") (pinfunction "1_1") (pintype "passive"))
      (node (ref "C296") (pin "1") (pinfunction "1_1") (pintype "passive"))
      (node (ref "C297") (pin "1") (pinfunction "1_1") (pintype "passive"))
      (node (ref "C298") (pin "1") (pinfunction "1_1") (pintype "passive"))
      (node (ref "C299") (pin "1") (pinfunction "1_1") (pintype "passive"))
      (node (ref "C300") (pin "1") (pinfunction "1_1") (pintype "passive"))
      (node (ref "C301") (pin "1") (pinfunction "1_1") (pintype "passive"))
      (node (ref "C302") (pin "1") (pinfunction "1_1") (pintype "passive"))
      (node (ref "C303") (pin "1") (pinfunction "1_1") (pintype "passive"))
      (node (ref "C304") (pin "1") (pinfunction "1_1") (pintype "passive"))
      (node (ref "C305") (pin "1") (pinfunction "1_1") (pintype "passive"))
      (node (ref "C306") (pin "1") (pinfunction "1_1") (pintype "passive"))
      (node (ref "C307") (pin "1") (pinfunction "1_1") (pintype "passive"))
      (node (ref "C308") (pin "1") (pinfunction "1_1") (pintype "passive"))
      (node (ref "C309") (pin "1") (pinfunction "1_1") (pintype "passive"))
      (node (ref "C310") (pin "1") (pinfunction "1_1") (pintype "passive"))
      (node (ref "C311") (pin "1") (pinfunction "1_1") (pintype "passive"))
      (node (ref "C312") (pin "1") (pinfunction "1_1") (pintype "passive"))
      (node (ref "C313") (pin "1") (pinfunction "1_1") (pintype "passive"))
      (node (ref "C314") (pin "1") (pinfunction "1_1") (pintype "passive"))
      (node (ref "C315") (pin "1") (pinfunction "1_1") (pintype "passive"))
      (node (ref "C316") (pin "1") (pinfunction "1_1") (pintype "passive"))
      (node (ref "C317") (pin "1") (pinfunction "1_1") (pintype "passive"))
      (node (ref "C318") (pin "1") (pinfunction "1_1") (pintype "passive"))
      (node (ref "C319") (pin "1") (pinfunction "1_1") (pintype "passive"))
      (node (ref "C320") (pin "1") (pinfunction "1_1") (pintype "passive"))
      (node (ref "C321") (pin "1") (pinfunction "1_1") (pintype "passive"))
      (node (ref "C322") (pin "1") (pinfunction "1_1") (pintype "passive"))
      (node (ref "C323") (pin "1") (pinfunction "1_1") (pintype "passive"))
      (node (ref "C324") (pin "1") (pinfunction "1_1") (pintype "passive"))
      (node (ref "C325") (pin "1") (pinfunction "1_1") (pintype "passive"))
      (node (ref "C326") (pin "1") (pinfunction "1_1") (pintype "passive"))
      (node (ref "C327") (pin "1") (pinfunction "1_1") (pintype "passive"))
      (node (ref "C328") (pin "1") (pinfunction "1_1") (pintype "passive"))
      (node (ref "C329") (pin "1") (pinfunction "1_1") (pintype "passive"))
      (node (ref "C330") (pin "1") (pinfunction "1_1") (pintype "passive"))
      (node (ref "D27") (pin "104") (pinfunction "VSS_104") (pintype "passive"))
      (node (ref "D27") (pin "106") (pinfunction "VSS_106") (pintype "passive"))
      (node (ref "D27") (pin "107") (pinfunction "VSS_107") (pintype "passive"))
      (node (ref "D27") (pin "110") (pinfunction "VSS_110") (pintype "passive"))
      (node (ref "D27") (pin "112") (pinfunction "VSS_112") (pintype "passive"))
      (node (ref "D27") (pin "113") (pinfunction "VSS_113") (pintype "passive"))
      (node (ref "D27") (pin "116") (pinfunction "VSS_116") (pintype "passive"))
      (node (ref "D27") (pin "118") (pinfunction "VSS_118") (pintype "passive"))
      (node (ref "D27") (pin "119") (pinfunction "VSS_119") (pintype "passive"))
      (node (ref "D27") (pin "12") (pinfunction "VSS_12") (pintype "passive"))
      (node (ref "D27") (pin "122") (pinfunction "VSS_122") (pintype "passive"))
      (node (ref "D27") (pin "124") (pinfunction "VSS_124") (pintype "passive"))
      (node (ref "D27") (pin "125") (pinfunction "VSS_125") (pintype "passive"))
      (node (ref "D27") (pin "128") (pinfunction "VSS_128") (pintype "passive"))
      (node (ref "D27") (pin "16") (pinfunction "VSS_16") (pintype "passive"))
      (node (ref "D27") (pin "20") (pinfunction "VSS_20") (pintype "passive"))
      (node (ref "D27") (pin "22") (pinfunction "VSS_22") (pintype "passive"))
      (node (ref "D27") (pin "26") (pinfunction "VSS_26") (pintype "passive"))
      (node (ref "D27") (pin "30") (pinfunction "VSS_30") (pintype "passive"))
      (node (ref "D27") (pin "36") (pinfunction "VSS_36") (pintype "passive"))
      (node (ref "D27") (pin "38") (pinfunction "VSS_38") (pintype "passive"))
      (node (ref "D27") (pin "43") (pinfunction "VSS_43") (pintype "passive"))
      (node (ref "D27") (pin "49") (pinfunction "VSS_49") (pintype "passive"))
      (node (ref "D27") (pin "5") (pinfunction "VSS_5") (pintype "passive"))
      (node (ref "D27") (pin "54") (pinfunction "VSS_54") (pintype "passive"))
      (node (ref "D27") (pin "59") (pinfunction "VSS_59") (pintype "passive"))
      (node (ref "D27") (pin "64") (pinfunction "VSS_64") (pintype "passive"))
      (node (ref "D27") (pin "70") (pinfunction "VSS_70") (pintype "passive"))
      (node (ref "D27") (pin "74") (pinfunction "VSS_74") (pintype "passive"))
      (node (ref "D27") (pin "78") (pinfunction "VSS_78") (pintype "passive"))
      (node (ref "D27") (pin "82") (pinfunction "VSS_82") (pintype "passive"))
      (node (ref "D27") (pin "91") (pinfunction "VSS_91") (pintype "passive"))
      (node (ref "D27") (pin "93") (pinfunction "VSS_93") (pintype "passive"))
      (node (ref "D27") (pin "97") (pinfunction "VSS_97") (pintype "passive"))
      (node (ref "D27") (pin "99") (pinfunction "VSS_99") (pintype "passive"))
      (node (ref "D7") (pin "K18") (pinfunction "IO_L3P_T0_DQS_PUDC_B_14_K18") (pintype "bidirectional"))
      (node (ref "R100") (pin "1") (pinfunction "1_1") (pintype "passive"))
      (node (ref "R100") (pin "3") (pinfunction "3_3") (pintype "passive"))
      (node (ref "R100") (pin "4") (pinfunction "4_4") (pintype "passive"))
      (node (ref "R106") (pin "7") (pinfunction "7_7") (pintype "passive"))
      (node (ref "R106") (pin "8") (pinfunction "8_8") (pintype "passive"))
      (node (ref "R107") (pin "1") (pinfunction "1_1") (pintype "passive"))
      (node (ref "R113") (pin "1") (pinfunction "1_1") (pintype "passive"))
      (node (ref "R113") (pin "2") (pinfunction "2_2") (pintype "passive"))
      (node (ref "R113") (pin "3") (pinfunction "3_3") (pintype "passive"))
      (node (ref "R116") (pin "2") (pinfunction "2_2") (pintype "passive"))
      (node (ref "R123") (pin "1") (pinfunction "1_1") (pintype "passive"))
      (node (ref "R124") (pin "1") (pinfunction "1_1") (pintype "passive"))
      (node (ref "R128") (pin "2") (pinfunction "2_2") (pintype "passive"))
      (node (ref "R99") (pin "2") (pinfunction "2_2") (pintype "passive"))
      (node (ref "X6") (pin "0") (pinfunction "SHLD_0") (pintype "passive"))
      (node (ref "X6") (pin "13") (pinfunction "LED1_13") (pintype "passive"))
    )
    (net (code "54") (name "Net-(D27B-COL)") (class "Default")
      (node (ref "D27") (pin "39") (pinfunction "COL_39") (pintype "passive"))
      (node (ref "R101") (pin "1") (pinfunction "1_1") (pintype "passive"))
      (node (ref "R103") (pin "8") (pinfunction "8_8") (pintype "passive"))
    )
    (net (code "55") (name "Net-(D27B-CRS)") (class "Default")
      (node (ref "D27") (pin "40") (pinfunction "CRS_40") (pintype "passive"))
      (node (ref "R103") (pin "7") (pinfunction "7_7") (pintype "passive"))
      (node (ref "R99") (pin "1") (pinfunction "1_1") (pintype "passive"))
    )
    (net (code "56") (name "Net-(D27B-GTX_CLK)") (class "Default")
      (node (ref "D27") (pin "79") (pinfunction "GTX_CLK_79") (pintype "passive"))
      (node (ref "R102") (pin "1") (pinfunction "1_1") (pintype "passive"))
    )
    (net (code "57") (name "Net-(D27B-RXD0)") (class "Default")
      (node (ref "D27") (pin "56") (pinfunction "RXD0_56") (pintype "passive"))
      (node (ref "R114") (pin "5") (pinfunction "5_5") (pintype "passive"))
    )
    (net (code "58") (name "Net-(D27B-RXD1)") (class "Default")
      (node (ref "D27") (pin "55") (pinfunction "RXD1_55") (pintype "passive"))
      (node (ref "R114") (pin "6") (pinfunction "6_6") (pintype "passive"))
    )
    (net (code "59") (name "Net-(D27B-RXD2)") (class "Default")
      (node (ref "D27") (pin "52") (pinfunction "RXD2_52") (pintype "passive"))
      (node (ref "R114") (pin "7") (pinfunction "7_7") (pintype "passive"))
    )
    (net (code "60") (name "Net-(D27B-RXD3)") (class "Default")
      (node (ref "D27") (pin "51") (pinfunction "RXD3_51") (pintype "passive"))
      (node (ref "R114") (pin "8") (pinfunction "8_8") (pintype "passive"))
    )
    (net (code "61") (name "Net-(D27B-RXD4)") (class "Default")
      (node (ref "D27") (pin "50") (pinfunction "RXD4_50") (pintype "passive"))
      (node (ref "R110") (pin "5") (pinfunction "5_5") (pintype "passive"))
    )
    (net (code "62") (name "Net-(D27B-RXD5)") (class "Default")
      (node (ref "D27") (pin "47") (pinfunction "RXD5_47") (pintype "passive"))
      (node (ref "R110") (pin "6") (pinfunction "6_6") (pintype "passive"))
    )
    (net (code "63") (name "Net-(D27B-RXD6)") (class "Default")
      (node (ref "D27") (pin "46") (pinfunction "RXD6_46") (pintype "passive"))
      (node (ref "R110") (pin "7") (pinfunction "7_7") (pintype "passive"))
    )
    (net (code "64") (name "Net-(D27B-RXD7)") (class "Default")
      (node (ref "D27") (pin "45") (pinfunction "RXD7_45") (pintype "passive"))
      (node (ref "R110") (pin "8") (pinfunction "8_8") (pintype "passive"))
    )
    (net (code "65") (name "Net-(D27B-RX_CLK)") (class "Default")
      (node (ref "D27") (pin "57") (pinfunction "RX_CLK_57") (pintype "passive"))
      (node (ref "R115") (pin "8") (pinfunction "8_8") (pintype "passive"))
    )
    (net (code "66") (name "Net-(D27B-RX_DV)") (class "Default")
      (node (ref "D27") (pin "44") (pinfunction "RX_DV_44") (pintype "passive"))
      (node (ref "R103") (pin "5") (pinfunction "5_5") (pintype "passive"))
    )
    (net (code "67") (name "Net-(D27B-RX_ER)") (class "Default")
      (node (ref "D27") (pin "41") (pinfunction "RX_ER_41") (pintype "passive"))
      (node (ref "R103") (pin "6") (pinfunction "6_6") (pintype "passive"))
    )
    (net (code "68") (name "Net-(D27B-TXD0)") (class "Default")
      (node (ref "D27") (pin "76") (pinfunction "TXD0_76") (pintype "passive"))
      (node (ref "R104") (pin "1") (pinfunction "1_1") (pintype "passive"))
    )
    (net (code "69") (name "Net-(D27B-TXD1)") (class "Default")
      (node (ref "D27") (pin "75") (pinfunction "TXD1_75") (pintype "passive"))
      (node (ref "R104") (pin "2") (pinfunction "2_2") (pintype "passive"))
    )
    (net (code "70") (name "Net-(D27B-TXD2)") (class "Default")
      (node (ref "D27") (pin "72") (pinfunction "TXD2_72") (pintype "passive"))
      (node (ref "R104") (pin "3") (pinfunction "3_3") (pintype "passive"))
    )
    (net (code "71") (name "Net-(D27B-TXD3)") (class "Default")
      (node (ref "D27") (pin "71") (pinfunction "TXD3_71") (pintype "passive"))
      (node (ref "R104") (pin "4") (pinfunction "4_4") (pintype "passive"))
    )
    (net (code "72") (name "Net-(D27B-TXD4)") (class "Default")
      (node (ref "D27") (pin "68") (pinfunction "TXD4_68") (pintype "passive"))
      (node (ref "R112") (pin "5") (pinfunction "5_5") (pintype "passive"))
    )
    (net (code "73") (name "Net-(D27B-TXD5)") (class "Default")
      (node (ref "D27") (pin "67") (pinfunction "TXD5_67") (pintype "passive"))
      (node (ref "R112") (pin "6") (pinfunction "6_6") (pintype "passive"))
    )
    (net (code "74") (name "Net-(D27B-TXD6)") (class "Default")
      (node (ref "D27") (pin "66") (pinfunction "TXD6_66") (pintype "passive"))
      (node (ref "R112") (pin "7") (pinfunction "7_7") (pintype "passive"))
    )
    (net (code "75") (name "Net-(D27B-TXD7)") (class "Default")
      (node (ref "D27") (pin "65") (pinfunction "TXD7_65") (pintype "passive"))
      (node (ref "R112") (pin "8") (pinfunction "8_8") (pintype "passive"))
    )
    (net (code "76") (name "Net-(D27B-TX_CLK)") (class "Default")
      (node (ref "D27") (pin "60") (pinfunction "TX_CLK_60") (pintype "passive"))
      (node (ref "R115") (pin "7") (pinfunction "7_7") (pintype "passive"))
      (node (ref "R116") (pin "1") (pinfunction "1_1") (pintype "passive"))
    )
    (net (code "77") (name "Net-(D27B-TX_EN)") (class "Default")
      (node (ref "D27") (pin "62") (pinfunction "TX_EN_62") (pintype "passive"))
      (node (ref "R115") (pin "5") (pinfunction "5_5") (pintype "passive"))
    )
    (net (code "78") (name "Net-(D27B-TX_ER)") (class "Default")
      (node (ref "D27") (pin "61") (pinfunction "TX_ER_61") (pintype "passive"))
      (node (ref "R115") (pin "6") (pinfunction "6_6") (pintype "passive"))
    )
    (net (code "79") (name "Net-(D27C-DUP_LED)") (class "Default")
      (node (ref "D27") (pin "13") (pinfunction "DUP_LED_13") (pintype "passive"))
      (node (ref "R107") (pin "5") (pinfunction "5_5") (pintype "passive"))
    )
    (net (code "80") (name "Net-(D27C-LNK1G_LED)") (class "Default")
      (node (ref "D27") (pin "10") (pinfunction "LNK1G_LED_10") (pintype "passive"))
      (node (ref "R107") (pin "6") (pinfunction "6_6") (pintype "passive"))
    )
    (net (code "81") (name "Net-(D27C-LNK10_LED)") (class "Default")
      (node (ref "D27") (pin "8") (pinfunction "LNK10_LED_8") (pintype "passive"))
      (node (ref "R107") (pin "8") (pinfunction "8_8") (pintype "passive"))
    )
    (net (code "82") (name "Net-(D27C-LNK100_LED)") (class "Default")
      (node (ref "D27") (pin "9") (pinfunction "LNK100_LED_9") (pintype "passive"))
      (node (ref "R107") (pin "7") (pinfunction "7_7") (pintype "passive"))
    )
    (net (code "83") (name "Net-(D27C-MAC_CLK_EN)") (class "Default")
      (node (ref "D27") (pin "88") (pinfunction "MAC_CLK_EN_88") (pintype "passive"))
      (node (ref "R106") (pin "4") (pinfunction "4_4") (pintype "passive"))
    )
    (net (code "84") (name "Net-(D27C-MDIX_EN)") (class "Default")
      (node (ref "D27") (pin "89") (pinfunction "MDIX_EN_89") (pintype "passive"))
      (node (ref "R106") (pin "3") (pinfunction "3_3") (pintype "passive"))
    )
    (net (code "85") (name "Net-(D27C-MULTI_EN)") (class "Default")
      (node (ref "D27") (pin "94") (pinfunction "MULTI_EN_94") (pintype "passive"))
      (node (ref "R106") (pin "2") (pinfunction "2_2") (pintype "passive"))
    )
    (net (code "86") (name "Net-(D27C-NON_IEEE)") (class "Default")
      (node (ref "D27") (pin "1") (pinfunction "NON_IEEE_1") (pintype "passive"))
      (node (ref "R100") (pin "8") (pinfunction "8_8") (pintype "passive"))
    )
    (net (code "87") (name "Net-(D27C-PHYADDR1)") (class "Default")
      (node (ref "D27") (pin "14") (pinfunction "PHYADDR1_14") (pintype "passive"))
      (node (ref "R113") (pin "8") (pinfunction "8_8") (pintype "passive"))
    )
    (net (code "88") (name "Net-(D27C-PHYADDR2)") (class "Default")
      (node (ref "D27") (pin "17") (pinfunction "PHYADDR2_17") (pintype "passive"))
      (node (ref "R113") (pin "7") (pinfunction "7_7") (pintype "passive"))
    )
    (net (code "89") (name "Net-(D27C-PHYADDR3)") (class "Default")
      (node (ref "D27") (pin "18") (pinfunction "PHYADDR3_18") (pintype "passive"))
      (node (ref "R113") (pin "6") (pinfunction "6_6") (pintype "passive"))
    )
    (net (code "90") (name "Net-(D27C-PHYADDR4)") (class "Default")
      (node (ref "D27") (pin "95") (pinfunction "PHYADDR4_95") (pintype "passive"))
      (node (ref "R106") (pin "1") (pinfunction "1_1") (pintype "passive"))
    )
    (net (code "91") (name "Net-(D27C-TX_TCLK)") (class "Default")
      (node (ref "D27") (pin "6") (pinfunction "TX_TCLK_6") (pintype "passive"))
      (node (ref "R100") (pin "6") (pinfunction "6_6") (pintype "passive"))
    )
    (net (code "92") (name "Net-(D27C-VDD_SEL)") (class "Default")
      (node (ref "D27") (pin "34") (pinfunction "VDD_SEL_34") (pintype "passive"))
      (node (ref "R105") (pin "1") (pinfunction "1_1") (pintype "passive"))
    )
    (net (code "93") (name "Net-(D27F-TRST)") (class "Default")
      (node (ref "D27") (pin "32") (pinfunction "TRST_32") (pintype "passive"))
      (node (ref "R123") (pin "2") (pinfunction "2_2") (pintype "passive"))
    )
    (net (code "94") (name "Net-(D27G-1V8_AVDD2)") (class "Default")
      (node (ref "C290") (pin "1") (pinfunction "1_1") (pintype "passive"))
      (node (ref "C291") (pin "1") (pinfunction "1_1") (pintype "passive"))
      (node (ref "D27") (pin "98") (pinfunction "1V8_AVDD2_98") (pintype "passive"))
      (node (ref "R126") (pin "2") (pinfunction "2_2") (pintype "passive"))
    )
    (net (code "95") (name "Net-(D27G-1V8_AVDD3)") (class "Default")
      (node (ref "C292") (pin "1") (pinfunction "1_1") (pintype "passive"))
      (node (ref "C293") (pin "1") (pinfunction "1_1") (pintype "passive"))
      (node (ref "D27") (pin "100") (pinfunction "1V8_AVDD3_100") (pintype "passive"))
      (node (ref "R127") (pin "2") (pinfunction "2_2") (pintype "passive"))
    )
    (net (code "96") (name "Net-(D27G-BG_REF)") (class "Default")
      (node (ref "D27") (pin "102") (pinfunction "BG_REF_102") (pintype "passive"))
      (node (ref "R128") (pin "1") (pinfunction "1_1") (pintype "passive"))
    )
    (net (code "97") (name "Net-(R124-Pad2)") (class "Default")
      (node (ref "R124") (pin "2") (pinfunction "2_2") (pintype "passive"))
      (node (ref "X6") (pin "15") (pinfunction "15_15") (pintype "passive"))
    )
    (net (code "98") (name "Net-(R125-Pad2)") (class "Default")
      (node (ref "R125") (pin "2") (pinfunction "2_2") (pintype "passive"))
      (node (ref "X6") (pin "14") (pinfunction "14_14") (pintype "passive"))
    )
    (net (code "99") (name "unconnected-(D7B-IO_0_14-PadK16)") (class "Default")
      (node (ref "D7") (pin "K16") (pinfunction "IO_0_14_K16") (pintype "bidirectional"))
    )
    (net (code "100") (name "unconnected-(D7B-IO_25_14-PadM16)") (class "Default")
      (node (ref "D7") (pin "M16") (pinfunction "IO_25_14_M16") (pintype "bidirectional"))
    )
    (net (code "101") (name "unconnected-(D7B-IO_L2P_T0_D02_14-PadG18)") (class "Default")
      (node (ref "D7") (pin "G18") (pinfunction "IO_L2P_T0_D02_14_G18") (pintype "bidirectional"))
    )
    (net (code "102") (name "unconnected-(D7B-IO_L5N_T0_D07_14-PadK19)") (class "Default")
      (node (ref "D7") (pin "K19") (pinfunction "IO_L5N_T0_D07_14_K19") (pintype "bidirectional"))
    )
    (net (code "103") (name "unconnected-(D7B-IO_L5P_T0_D06_14-PadL18)") (class "Default")
      (node (ref "D7") (pin "L18") (pinfunction "IO_L5P_T0_D06_14_L18") (pintype "bidirectional"))
    )
    (net (code "104") (name "unconnected-(D7B-IO_L6N_T0_D08_VREF_14-PadK17)") (class "Default")
      (node (ref "D7") (pin "K17") (pinfunction "IO_L6N_T0_D08_VREF_14_K17") (pintype "bidirectional"))
    )
    (net (code "105") (name "unconnected-(D7B-IO_L11N_T1_SRCC_14-PadH20)") (class "Default")
      (node (ref "D7") (pin "H20") (pinfunction "IO_L11N_T1_SRCC_14_H20") (pintype "bidirectional+no_connect"))
    )
    (net (code "106") (name "unconnected-(D7B-IO_L12N_T1_MRCC_14-PadL20)") (class "Default")
      (node (ref "D7") (pin "L20") (pinfunction "IO_L12N_T1_MRCC_14_L20") (pintype "bidirectional+no_connect"))
    )
    (net (code "107") (name "unconnected-(D7B-IO_L13N_T2_MRCC_14-PadN19)") (class "Default")
      (node (ref "D7") (pin "N19") (pinfunction "IO_L13N_T2_MRCC_14_N19") (pintype "bidirectional+no_connect"))
    )
    (net (code "108") (name "unconnected-(D7B-IO_L14N_T2_SRCC_14-PadM18)") (class "Default")
      (node (ref "D7") (pin "M18") (pinfunction "IO_L14N_T2_SRCC_14_M18") (pintype "bidirectional+no_connect"))
    )
    (net (code "109") (name "unconnected-(D7B-IO_L19N_T3_A09_D25_VREF_14-PadR19)") (class "Default")
      (node (ref "D7") (pin "R19") (pinfunction "IO_L19N_T3_A09_D25_VREF_14_R19") (pintype "bidirectional"))
    )
    (net (code "110") (name "unconnected-(D7B-IO_L19P_T3_A10_D26_14-PadR18)") (class "Default")
      (node (ref "D7") (pin "R18") (pinfunction "IO_L19P_T3_A10_D26_14_R18") (pintype "bidirectional"))
    )
    (net (code "111") (name "unconnected-(D7B-IO_L21N_T3_DQS_A06_D22_14-PadP17)") (class "Default")
      (node (ref "D7") (pin "P17") (pinfunction "IO_L21N_T3_DQS_A06_D22_14_P17") (pintype "bidirectional"))
    )
    (net (code "112") (name "unconnected-(D7B-IO_L21P_T3_DQS_14-PadR17)") (class "Default")
      (node (ref "D7") (pin "R17") (pinfunction "IO_L21P_T3_DQS_14_R17") (pintype "bidirectional"))
    )
    (net (code "113") (name "unconnected-(D7B-IO_L23N_T3_A02_D18_14-PadN17)") (class "Default")
      (node (ref "D7") (pin "N17") (pinfunction "IO_L23N_T3_A02_D18_14_N17") (pintype "bidirectional"))
    )
    (net (code "114") (name "unconnected-(D7B-IO_L23P_T3_A03_D19_14-PadP16)") (class "Default")
      (node (ref "D7") (pin "P16") (pinfunction "IO_L23P_T3_A03_D19_14_P16") (pintype "bidirectional"))
    )
    (net (code "115") (name "unconnected-(D27F-TCK-Pad24)") (class "Default")
      (node (ref "D27") (pin "24") (pinfunction "TCK_24") (pintype "passive"))
    )
    (net (code "116") (name "unconnected-(D27F-TDI-Pad31)") (class "Default")
      (node (ref "D27") (pin "31") (pinfunction "TDI_31") (pintype "passive"))
    )
    (net (code "117") (name "unconnected-(D27F-TDO-Pad28)") (class "Default")
      (node (ref "D27") (pin "28") (pinfunction "TDO_28") (pintype "passive"))
    )
    (net (code "118") (name "unconnected-(D27F-TMS-Pad27)") (class "Default")
      (node (ref "D27") (pin "27") (pinfunction "TMS_27") (pintype "passive"))
    )
    (net (code "119") (name "unconnected-(D27G-RESERVED-Pad2)") (class "Default")
      (node (ref "D27") (pin "2") (pinfunction "RESERVED_2") (pintype "passive"))
    )
    (net (code "120") (name "unconnected-(D27G-RESERVED-Pad23)") (class "Default")
      (node (ref "D27") (pin "23") (pinfunction "RESERVED_23") (pintype "passive"))
    )
    (net (code "121") (name "unconnected-(D27G-RESERVED-Pad84)") (class "Default")
      (node (ref "D27") (pin "84") (pinfunction "RESERVED_84") (pintype "passive"))
    )
    (net (code "122") (name "unconnected-(R113-Pad4)") (class "Default")
      (node (ref "R113") (pin "4") (pinfunction "4_4") (pintype "passive"))
    )
    (net (code "123") (name "unconnected-(R113-Pad5)") (class "Default")
      (node (ref "R113") (pin "5") (pinfunction "5_5") (pintype "passive"))
    )
  )
)
